# charlie_array_1206_v1.net
KiCad netlist of a schematic drawn in EAGLE
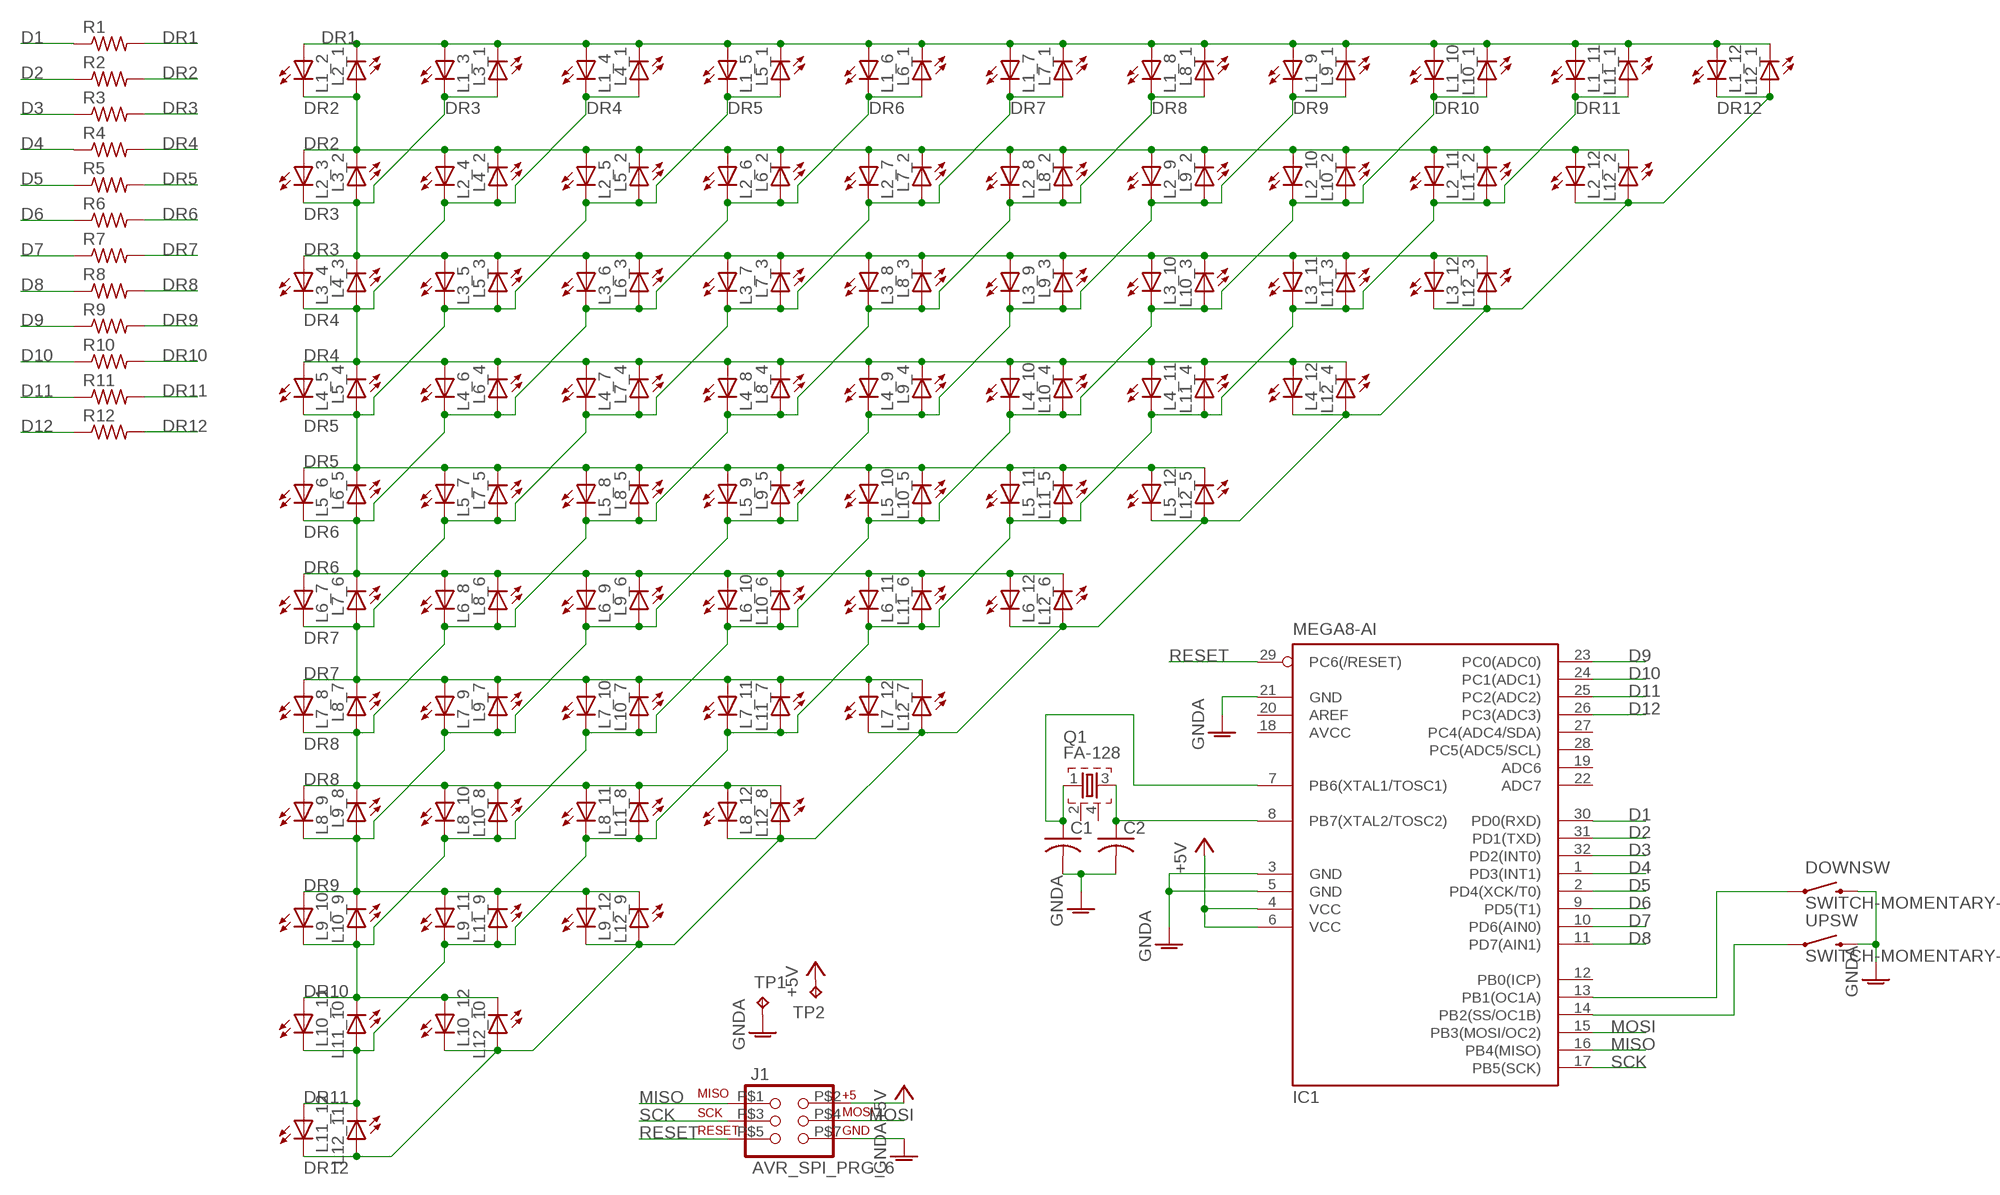
[diagram p0: schematic, sheet 1]

(export (version "E")
  (design (tool "Eeschema 10.0.6"))
  (components
    (comp (ref "C1")
      (value "C-USC0603")
      (footprint "eagle-import:C0603")
      (libsource (lib "eagle-import") (part "C-USC0603"))
    )
    (comp (ref "C2")
      (value "C-USC0603")
      (footprint "eagle-import:C0603")
      (libsource (lib "eagle-import") (part "C-USC0603"))
    )
    (comp (ref "DOWNSW")
      (value "SWITCH-MOMENTARY-2")
      (footprint "eagle-import:TACTILE_SWITCH_TALL")
      (libsource (lib "eagle-import") (part "SWITCH-MOMENTARY-2"))
    )
    (comp (ref "IC1")
      (value "MEGA8-AI")
      (footprint "eagle-import:TQFP32-08")
      (fields (field (name "MPN") "ATMEGA8-16AU"))
      (libsource (lib "eagle-import") (part "MEGA8-AI"))
    )
    (comp (ref "J1")
      (value "AVR_SPI_PRG_6")
      (footprint "eagle-import:2X3_ICSP_SMD")
      (libsource (lib "eagle-import") (part "AVR_SPI_PRG_6"))
    )
    (comp (ref "L1_2")
      (value "LEDCHIPLED_1206")
      (footprint "eagle-import:CHIPLED_1206")
      (libsource (lib "eagle-import") (part "LEDCHIPLED_1206"))
    )
    (comp (ref "L1_3")
      (value "LEDCHIPLED_1206")
      (footprint "eagle-import:CHIPLED_1206")
      (libsource (lib "eagle-import") (part "LEDCHIPLED_1206"))
    )
    (comp (ref "L1_4")
      (value "LEDCHIPLED_1206")
      (footprint "eagle-import:CHIPLED_1206")
      (libsource (lib "eagle-import") (part "LEDCHIPLED_1206"))
    )
    (comp (ref "L1_5")
      (value "LEDCHIPLED_1206")
      (footprint "eagle-import:CHIPLED_1206")
      (libsource (lib "eagle-import") (part "LEDCHIPLED_1206"))
    )
    (comp (ref "L1_6")
      (value "LEDCHIPLED_1206")
      (footprint "eagle-import:CHIPLED_1206")
      (libsource (lib "eagle-import") (part "LEDCHIPLED_1206"))
    )
    (comp (ref "L1_7")
      (value "LEDCHIPLED_1206")
      (footprint "eagle-import:CHIPLED_1206")
      (libsource (lib "eagle-import") (part "LEDCHIPLED_1206"))
    )
    (comp (ref "L1_8")
      (value "LEDCHIPLED_1206")
      (footprint "eagle-import:CHIPLED_1206")
      (libsource (lib "eagle-import") (part "LEDCHIPLED_1206"))
    )
    (comp (ref "L1_9")
      (value "LEDCHIPLED_1206")
      (footprint "eagle-import:CHIPLED_1206")
      (libsource (lib "eagle-import") (part "LEDCHIPLED_1206"))
    )
    (comp (ref "L1_10")
      (value "LEDCHIPLED_1206")
      (footprint "eagle-import:CHIPLED_1206")
      (libsource (lib "eagle-import") (part "LEDCHIPLED_1206"))
    )
    (comp (ref "L1_11")
      (value "LEDCHIPLED_1206")
      (footprint "eagle-import:CHIPLED_1206")
      (libsource (lib "eagle-import") (part "LEDCHIPLED_1206"))
    )
    (comp (ref "L1_12")
      (value "LEDCHIPLED_1206")
      (footprint "eagle-import:CHIPLED_1206")
      (libsource (lib "eagle-import") (part "LEDCHIPLED_1206"))
    )
    (comp (ref "L2_1")
      (value "LEDCHIPLED_1206")
      (footprint "eagle-import:CHIPLED_1206")
      (libsource (lib "eagle-import") (part "LEDCHIPLED_1206"))
    )
    (comp (ref "L2_3")
      (value "LEDCHIPLED_1206")
      (footprint "eagle-import:CHIPLED_1206")
      (libsource (lib "eagle-import") (part "LEDCHIPLED_1206"))
    )
    (comp (ref "L2_4")
      (value "LEDCHIPLED_1206")
      (footprint "eagle-import:CHIPLED_1206")
      (libsource (lib "eagle-import") (part "LEDCHIPLED_1206"))
    )
    (comp (ref "L2_5")
      (value "LEDCHIPLED_1206")
      (footprint "eagle-import:CHIPLED_1206")
      (libsource (lib "eagle-import") (part "LEDCHIPLED_1206"))
    )
    (comp (ref "L2_6")
      (value "LEDCHIPLED_1206")
      (footprint "eagle-import:CHIPLED_1206")
      (libsource (lib "eagle-import") (part "LEDCHIPLED_1206"))
    )
    (comp (ref "L2_7")
      (value "LEDCHIPLED_1206")
      (footprint "eagle-import:CHIPLED_1206")
      (libsource (lib "eagle-import") (part "LEDCHIPLED_1206"))
    )
    (comp (ref "L2_8")
      (value "LEDCHIPLED_1206")
      (footprint "eagle-import:CHIPLED_1206")
      (libsource (lib "eagle-import") (part "LEDCHIPLED_1206"))
    )
    (comp (ref "L2_9")
      (value "LEDCHIPLED_1206")
      (footprint "eagle-import:CHIPLED_1206")
      (libsource (lib "eagle-import") (part "LEDCHIPLED_1206"))
    )
    (comp (ref "L2_10")
      (value "LEDCHIPLED_1206")
      (footprint "eagle-import:CHIPLED_1206")
      (libsource (lib "eagle-import") (part "LEDCHIPLED_1206"))
    )
    (comp (ref "L2_11")
      (value "LEDCHIPLED_1206")
      (footprint "eagle-import:CHIPLED_1206")
      (libsource (lib "eagle-import") (part "LEDCHIPLED_1206"))
    )
    (comp (ref "L2_12")
      (value "LEDCHIPLED_1206")
      (footprint "eagle-import:CHIPLED_1206")
      (libsource (lib "eagle-import") (part "LEDCHIPLED_1206"))
    )
    (comp (ref "L3_1")
      (value "LEDCHIPLED_1206")
      (footprint "eagle-import:CHIPLED_1206")
      (libsource (lib "eagle-import") (part "LEDCHIPLED_1206"))
    )
    (comp (ref "L3_2")
      (value "LEDCHIPLED_1206")
      (footprint "eagle-import:CHIPLED_1206")
      (libsource (lib "eagle-import") (part "LEDCHIPLED_1206"))
    )
    (comp (ref "L3_4")
      (value "LEDCHIPLED_1206")
      (footprint "eagle-import:CHIPLED_1206")
      (libsource (lib "eagle-import") (part "LEDCHIPLED_1206"))
    )
    (comp (ref "L3_5")
      (value "LEDCHIPLED_1206")
      (footprint "eagle-import:CHIPLED_1206")
      (libsource (lib "eagle-import") (part "LEDCHIPLED_1206"))
    )
    (comp (ref "L3_6")
      (value "LEDCHIPLED_1206")
      (footprint "eagle-import:CHIPLED_1206")
      (libsource (lib "eagle-import") (part "LEDCHIPLED_1206"))
    )
    (comp (ref "L3_7")
      (value "LEDCHIPLED_1206")
      (footprint "eagle-import:CHIPLED_1206")
      (libsource (lib "eagle-import") (part "LEDCHIPLED_1206"))
    )
    (comp (ref "L3_8")
      (value "LEDCHIPLED_1206")
      (footprint "eagle-import:CHIPLED_1206")
      (libsource (lib "eagle-import") (part "LEDCHIPLED_1206"))
    )
    (comp (ref "L3_9")
      (value "LEDCHIPLED_1206")
      (footprint "eagle-import:CHIPLED_1206")
      (libsource (lib "eagle-import") (part "LEDCHIPLED_1206"))
    )
    (comp (ref "L3_10")
      (value "LEDCHIPLED_1206")
      (footprint "eagle-import:CHIPLED_1206")
      (libsource (lib "eagle-import") (part "LEDCHIPLED_1206"))
    )
    (comp (ref "L3_11")
      (value "LEDCHIPLED_1206")
      (footprint "eagle-import:CHIPLED_1206")
      (libsource (lib "eagle-import") (part "LEDCHIPLED_1206"))
    )
    (comp (ref "L3_12")
      (value "LEDCHIPLED_1206")
      (footprint "eagle-import:CHIPLED_1206")
      (libsource (lib "eagle-import") (part "LEDCHIPLED_1206"))
    )
    (comp (ref "L4_1")
      (value "LEDCHIPLED_1206")
      (footprint "eagle-import:CHIPLED_1206")
      (libsource (lib "eagle-import") (part "LEDCHIPLED_1206"))
    )
    (comp (ref "L4_2")
      (value "LEDCHIPLED_1206")
      (footprint "eagle-import:CHIPLED_1206")
      (libsource (lib "eagle-import") (part "LEDCHIPLED_1206"))
    )
    (comp (ref "L4_3")
      (value "LEDCHIPLED_1206")
      (footprint "eagle-import:CHIPLED_1206")
      (libsource (lib "eagle-import") (part "LEDCHIPLED_1206"))
    )
    (comp (ref "L4_5")
      (value "LEDCHIPLED_1206")
      (footprint "eagle-import:CHIPLED_1206")
      (libsource (lib "eagle-import") (part "LEDCHIPLED_1206"))
    )
    (comp (ref "L4_6")
      (value "LEDCHIPLED_1206")
      (footprint "eagle-import:CHIPLED_1206")
      (libsource (lib "eagle-import") (part "LEDCHIPLED_1206"))
    )
    (comp (ref "L4_7")
      (value "LEDCHIPLED_1206")
      (footprint "eagle-import:CHIPLED_1206")
      (libsource (lib "eagle-import") (part "LEDCHIPLED_1206"))
    )
    (comp (ref "L4_8")
      (value "LEDCHIPLED_1206")
      (footprint "eagle-import:CHIPLED_1206")
      (libsource (lib "eagle-import") (part "LEDCHIPLED_1206"))
    )
    (comp (ref "L4_9")
      (value "LEDCHIPLED_1206")
      (footprint "eagle-import:CHIPLED_1206")
      (libsource (lib "eagle-import") (part "LEDCHIPLED_1206"))
    )
    (comp (ref "L4_10")
      (value "LEDCHIPLED_1206")
      (footprint "eagle-import:CHIPLED_1206")
      (libsource (lib "eagle-import") (part "LEDCHIPLED_1206"))
    )
    (comp (ref "L4_11")
      (value "LEDCHIPLED_1206")
      (footprint "eagle-import:CHIPLED_1206")
      (libsource (lib "eagle-import") (part "LEDCHIPLED_1206"))
    )
    (comp (ref "L4_12")
      (value "LEDCHIPLED_1206")
      (footprint "eagle-import:CHIPLED_1206")
      (libsource (lib "eagle-import") (part "LEDCHIPLED_1206"))
    )
    (comp (ref "L5_1")
      (value "LEDCHIPLED_1206")
      (footprint "eagle-import:CHIPLED_1206")
      (libsource (lib "eagle-import") (part "LEDCHIPLED_1206"))
    )
    (comp (ref "L5_2")
      (value "LEDCHIPLED_1206")
      (footprint "eagle-import:CHIPLED_1206")
      (libsource (lib "eagle-import") (part "LEDCHIPLED_1206"))
    )
    (comp (ref "L5_3")
      (value "LEDCHIPLED_1206")
      (footprint "eagle-import:CHIPLED_1206")
      (libsource (lib "eagle-import") (part "LEDCHIPLED_1206"))
    )
    (comp (ref "L5_4")
      (value "LEDCHIPLED_1206")
      (footprint "eagle-import:CHIPLED_1206")
      (libsource (lib "eagle-import") (part "LEDCHIPLED_1206"))
    )
    (comp (ref "L5_6")
      (value "LEDCHIPLED_1206")
      (footprint "eagle-import:CHIPLED_1206")
      (libsource (lib "eagle-import") (part "LEDCHIPLED_1206"))
    )
    (comp (ref "L5_7")
      (value "LEDCHIPLED_1206")
      (footprint "eagle-import:CHIPLED_1206")
      (libsource (lib "eagle-import") (part "LEDCHIPLED_1206"))
    )
    (comp (ref "L5_8")
      (value "LEDCHIPLED_1206")
      (footprint "eagle-import:CHIPLED_1206")
      (libsource (lib "eagle-import") (part "LEDCHIPLED_1206"))
    )
    (comp (ref "L5_9")
      (value "LEDCHIPLED_1206")
      (footprint "eagle-import:CHIPLED_1206")
      (libsource (lib "eagle-import") (part "LEDCHIPLED_1206"))
    )
    (comp (ref "L5_10")
      (value "LEDCHIPLED_1206")
      (footprint "eagle-import:CHIPLED_1206")
      (libsource (lib "eagle-import") (part "LEDCHIPLED_1206"))
    )
    (comp (ref "L5_11")
      (value "LEDCHIPLED_1206")
      (footprint "eagle-import:CHIPLED_1206")
      (libsource (lib "eagle-import") (part "LEDCHIPLED_1206"))
    )
    (comp (ref "L5_12")
      (value "LEDCHIPLED_1206")
      (footprint "eagle-import:CHIPLED_1206")
      (libsource (lib "eagle-import") (part "LEDCHIPLED_1206"))
    )
    (comp (ref "L6_1")
      (value "LEDCHIPLED_1206")
      (footprint "eagle-import:CHIPLED_1206")
      (libsource (lib "eagle-import") (part "LEDCHIPLED_1206"))
    )
    (comp (ref "L6_2")
      (value "LEDCHIPLED_1206")
      (footprint "eagle-import:CHIPLED_1206")
      (libsource (lib "eagle-import") (part "LEDCHIPLED_1206"))
    )
    (comp (ref "L6_3")
      (value "LEDCHIPLED_1206")
      (footprint "eagle-import:CHIPLED_1206")
      (libsource (lib "eagle-import") (part "LEDCHIPLED_1206"))
    )
    (comp (ref "L6_4")
      (value "LEDCHIPLED_1206")
      (footprint "eagle-import:CHIPLED_1206")
      (libsource (lib "eagle-import") (part "LEDCHIPLED_1206"))
    )
    (comp (ref "L6_5")
      (value "LEDCHIPLED_1206")
      (footprint "eagle-import:CHIPLED_1206")
      (libsource (lib "eagle-import") (part "LEDCHIPLED_1206"))
    )
    (comp (ref "L6_7")
      (value "LEDCHIPLED_1206")
      (footprint "eagle-import:CHIPLED_1206")
      (libsource (lib "eagle-import") (part "LEDCHIPLED_1206"))
    )
    (comp (ref "L6_8")
      (value "LEDCHIPLED_1206")
      (footprint "eagle-import:CHIPLED_1206")
      (libsource (lib "eagle-import") (part "LEDCHIPLED_1206"))
    )
    (comp (ref "L6_9")
      (value "LEDCHIPLED_1206")
      (footprint "eagle-import:CHIPLED_1206")
      (libsource (lib "eagle-import") (part "LEDCHIPLED_1206"))
    )
    (comp (ref "L6_10")
      (value "LEDCHIPLED_1206")
      (footprint "eagle-import:CHIPLED_1206")
      (libsource (lib "eagle-import") (part "LEDCHIPLED_1206"))
    )
    (comp (ref "L6_11")
      (value "LEDCHIPLED_1206")
      (footprint "eagle-import:CHIPLED_1206")
      (libsource (lib "eagle-import") (part "LEDCHIPLED_1206"))
    )
    (comp (ref "L6_12")
      (value "LEDCHIPLED_1206")
      (footprint "eagle-import:CHIPLED_1206")
      (libsource (lib "eagle-import") (part "LEDCHIPLED_1206"))
    )
    (comp (ref "L7_1")
      (value "LEDCHIPLED_1206")
      (footprint "eagle-import:CHIPLED_1206")
      (libsource (lib "eagle-import") (part "LEDCHIPLED_1206"))
    )
    (comp (ref "L7_2")
      (value "LEDCHIPLED_1206")
      (footprint "eagle-import:CHIPLED_1206")
      (libsource (lib "eagle-import") (part "LEDCHIPLED_1206"))
    )
    (comp (ref "L7_3")
      (value "LEDCHIPLED_1206")
      (footprint "eagle-import:CHIPLED_1206")
      (libsource (lib "eagle-import") (part "LEDCHIPLED_1206"))
    )
    (comp (ref "L7_4")
      (value "LEDCHIPLED_1206")
      (footprint "eagle-import:CHIPLED_1206")
      (libsource (lib "eagle-import") (part "LEDCHIPLED_1206"))
    )
    (comp (ref "L7_5")
      (value "LEDCHIPLED_1206")
      (footprint "eagle-import:CHIPLED_1206")
      (libsource (lib "eagle-import") (part "LEDCHIPLED_1206"))
    )
    (comp (ref "L7_6")
      (value "LEDCHIPLED_1206")
      (footprint "eagle-import:CHIPLED_1206")
      (libsource (lib "eagle-import") (part "LEDCHIPLED_1206"))
    )
    (comp (ref "L7_8")
      (value "LEDCHIPLED_1206")
      (footprint "eagle-import:CHIPLED_1206")
      (libsource (lib "eagle-import") (part "LEDCHIPLED_1206"))
    )
    (comp (ref "L7_9")
      (value "LEDCHIPLED_1206")
      (footprint "eagle-import:CHIPLED_1206")
      (libsource (lib "eagle-import") (part "LEDCHIPLED_1206"))
    )
    (comp (ref "L7_10")
      (value "LEDCHIPLED_1206")
      (footprint "eagle-import:CHIPLED_1206")
      (libsource (lib "eagle-import") (part "LEDCHIPLED_1206"))
    )
    (comp (ref "L7_11")
      (value "LEDCHIPLED_1206")
      (footprint "eagle-import:CHIPLED_1206")
      (libsource (lib "eagle-import") (part "LEDCHIPLED_1206"))
    )
    (comp (ref "L7_12")
      (value "LEDCHIPLED_1206")
      (footprint "eagle-import:CHIPLED_1206")
      (libsource (lib "eagle-import") (part "LEDCHIPLED_1206"))
    )
    (comp (ref "L8_1")
      (value "LEDCHIPLED_1206")
      (footprint "eagle-import:CHIPLED_1206")
      (libsource (lib "eagle-import") (part "LEDCHIPLED_1206"))
    )
    (comp (ref "L8_2")
      (value "LEDCHIPLED_1206")
      (footprint "eagle-import:CHIPLED_1206")
      (libsource (lib "eagle-import") (part "LEDCHIPLED_1206"))
    )
    (comp (ref "L8_3")
      (value "LEDCHIPLED_1206")
      (footprint "eagle-import:CHIPLED_1206")
      (libsource (lib "eagle-import") (part "LEDCHIPLED_1206"))
    )
    (comp (ref "L8_4")
      (value "LEDCHIPLED_1206")
      (footprint "eagle-import:CHIPLED_1206")
      (libsource (lib "eagle-import") (part "LEDCHIPLED_1206"))
    )
    (comp (ref "L8_5")
      (value "LEDCHIPLED_1206")
      (footprint "eagle-import:CHIPLED_1206")
      (libsource (lib "eagle-import") (part "LEDCHIPLED_1206"))
    )
    (comp (ref "L8_6")
      (value "LEDCHIPLED_1206")
      (footprint "eagle-import:CHIPLED_1206")
      (libsource (lib "eagle-import") (part "LEDCHIPLED_1206"))
    )
    (comp (ref "L8_7")
      (value "LEDCHIPLED_1206")
      (footprint "eagle-import:CHIPLED_1206")
      (libsource (lib "eagle-import") (part "LEDCHIPLED_1206"))
    )
    (comp (ref "L8_9")
      (value "LEDCHIPLED_1206")
      (footprint "eagle-import:CHIPLED_1206")
      (libsource (lib "eagle-import") (part "LEDCHIPLED_1206"))
    )
    (comp (ref "L8_10")
      (value "LEDCHIPLED_1206")
      (footprint "eagle-import:CHIPLED_1206")
      (libsource (lib "eagle-import") (part "LEDCHIPLED_1206"))
    )
    (comp (ref "L8_11")
      (value "LEDCHIPLED_1206")
      (footprint "eagle-import:CHIPLED_1206")
      (libsource (lib "eagle-import") (part "LEDCHIPLED_1206"))
    )
    (comp (ref "L8_12")
      (value "LEDCHIPLED_1206")
      (footprint "eagle-import:CHIPLED_1206")
      (libsource (lib "eagle-import") (part "LEDCHIPLED_1206"))
    )
    (comp (ref "L9_1")
      (value "LEDCHIPLED_1206")
      (footprint "eagle-import:CHIPLED_1206")
      (libsource (lib "eagle-import") (part "LEDCHIPLED_1206"))
    )
    (comp (ref "L9_2")
      (value "LEDCHIPLED_1206")
      (footprint "eagle-import:CHIPLED_1206")
      (libsource (lib "eagle-import") (part "LEDCHIPLED_1206"))
    )
    (comp (ref "L9_3")
      (value "LEDCHIPLED_1206")
      (footprint "eagle-import:CHIPLED_1206")
      (libsource (lib "eagle-import") (part "LEDCHIPLED_1206"))
    )
    (comp (ref "L9_4")
      (value "LEDCHIPLED_1206")
      (footprint "eagle-import:CHIPLED_1206")
      (libsource (lib "eagle-import") (part "LEDCHIPLED_1206"))
    )
    (comp (ref "L9_5")
      (value "LEDCHIPLED_1206")
      (footprint "eagle-import:CHIPLED_1206")
      (libsource (lib "eagle-import") (part "LEDCHIPLED_1206"))
    )
    (comp (ref "L9_6")
      (value "LEDCHIPLED_1206")
      (footprint "eagle-import:CHIPLED_1206")
      (libsource (lib "eagle-import") (part "LEDCHIPLED_1206"))
    )
    (comp (ref "L9_7")
      (value "LEDCHIPLED_1206")
      (footprint "eagle-import:CHIPLED_1206")
      (libsource (lib "eagle-import") (part "LEDCHIPLED_1206"))
    )
    (comp (ref "L9_8")
      (value "LEDCHIPLED_1206")
      (footprint "eagle-import:CHIPLED_1206")
      (libsource (lib "eagle-import") (part "LEDCHIPLED_1206"))
    )
    (comp (ref "L9_10")
      (value "LEDCHIPLED_1206")
      (footprint "eagle-import:CHIPLED_1206")
      (libsource (lib "eagle-import") (part "LEDCHIPLED_1206"))
    )
    (comp (ref "L9_11")
      (value "LEDCHIPLED_1206")
      (footprint "eagle-import:CHIPLED_1206")
      (libsource (lib "eagle-import") (part "LEDCHIPLED_1206"))
    )
    (comp (ref "L9_12")
      (value "LEDCHIPLED_1206")
      (footprint "eagle-import:CHIPLED_1206")
      (libsource (lib "eagle-import") (part "LEDCHIPLED_1206"))
    )
    (comp (ref "L10_1")
      (value "LEDCHIPLED_1206")
      (footprint "eagle-import:CHIPLED_1206")
      (libsource (lib "eagle-import") (part "LEDCHIPLED_1206"))
    )
    (comp (ref "L10_2")
      (value "LEDCHIPLED_1206")
      (footprint "eagle-import:CHIPLED_1206")
      (libsource (lib "eagle-import") (part "LEDCHIPLED_1206"))
    )
    (comp (ref "L10_3")
      (value "LEDCHIPLED_1206")
      (footprint "eagle-import:CHIPLED_1206")
      (libsource (lib "eagle-import") (part "LEDCHIPLED_1206"))
    )
    (comp (ref "L10_4")
      (value "LEDCHIPLED_1206")
      (footprint "eagle-import:CHIPLED_1206")
      (libsource (lib "eagle-import") (part "LEDCHIPLED_1206"))
    )
    (comp (ref "L10_5")
      (value "LEDCHIPLED_1206")
      (footprint "eagle-import:CHIPLED_1206")
      (libsource (lib "eagle-import") (part "LEDCHIPLED_1206"))
    )
    (comp (ref "L10_6")
      (value "LEDCHIPLED_1206")
      (footprint "eagle-import:CHIPLED_1206")
      (libsource (lib "eagle-import") (part "LEDCHIPLED_1206"))
    )
    (comp (ref "L10_7")
      (value "LEDCHIPLED_1206")
      (footprint "eagle-import:CHIPLED_1206")
      (libsource (lib "eagle-import") (part "LEDCHIPLED_1206"))
    )
    (comp (ref "L10_8")
      (value "LEDCHIPLED_1206")
      (footprint "eagle-import:CHIPLED_1206")
      (libsource (lib "eagle-import") (part "LEDCHIPLED_1206"))
    )
    (comp (ref "L10_9")
      (value "LEDCHIPLED_1206")
      (footprint "eagle-import:CHIPLED_1206")
      (libsource (lib "eagle-import") (part "LEDCHIPLED_1206"))
    )
    (comp (ref "L10_11")
      (value "LEDCHIPLED_1206")
      (footprint "eagle-import:CHIPLED_1206")
      (libsource (lib "eagle-import") (part "LEDCHIPLED_1206"))
    )
    (comp (ref "L10_12")
      (value "LEDCHIPLED_1206")
      (footprint "eagle-import:CHIPLED_1206")
      (libsource (lib "eagle-import") (part "LEDCHIPLED_1206"))
    )
    (comp (ref "L11_1")
      (value "LEDCHIPLED_1206")
      (footprint "eagle-import:CHIPLED_1206")
      (libsource (lib "eagle-import") (part "LEDCHIPLED_1206"))
    )
    (comp (ref "L11_2")
      (value "LEDCHIPLED_1206")
      (footprint "eagle-import:CHIPLED_1206")
      (libsource (lib "eagle-import") (part "LEDCHIPLED_1206"))
    )
    (comp (ref "L11_3")
      (value "LEDCHIPLED_1206")
      (footprint "eagle-import:CHIPLED_1206")
      (libsource (lib "eagle-import") (part "LEDCHIPLED_1206"))
    )
    (comp (ref "L11_4")
      (value "LEDCHIPLED_1206")
      (footprint "eagle-import:CHIPLED_1206")
      (libsource (lib "eagle-import") (part "LEDCHIPLED_1206"))
    )
    (comp (ref "L11_5")
      (value "LEDCHIPLED_1206")
      (footprint "eagle-import:CHIPLED_1206")
      (libsource (lib "eagle-import") (part "LEDCHIPLED_1206"))
    )
    (comp (ref "L11_6")
      (value "LEDCHIPLED_1206")
      (footprint "eagle-import:CHIPLED_1206")
      (libsource (lib "eagle-import") (part "LEDCHIPLED_1206"))
    )
    (comp (ref "L11_7")
      (value "LEDCHIPLED_1206")
      (footprint "eagle-import:CHIPLED_1206")
      (libsource (lib "eagle-import") (part "LEDCHIPLED_1206"))
    )
    (comp (ref "L11_8")
      (value "LEDCHIPLED_1206")
      (footprint "eagle-import:CHIPLED_1206")
      (libsource (lib "eagle-import") (part "LEDCHIPLED_1206"))
    )
    (comp (ref "L11_9")
      (value "LEDCHIPLED_1206")
      (footprint "eagle-import:CHIPLED_1206")
      (libsource (lib "eagle-import") (part "LEDCHIPLED_1206"))
    )
    (comp (ref "L11_10")
      (value "LEDCHIPLED_1206")
      (footprint "eagle-import:CHIPLED_1206")
      (libsource (lib "eagle-import") (part "LEDCHIPLED_1206"))
    )
    (comp (ref "L11_12")
      (value "LEDCHIPLED_1206")
      (footprint "eagle-import:CHIPLED_1206")
      (libsource (lib "eagle-import") (part "LEDCHIPLED_1206"))
    )
    (comp (ref "L12_1")
      (value "LEDCHIPLED_1206")
      (footprint "eagle-import:CHIPLED_1206")
      (libsource (lib "eagle-import") (part "LEDCHIPLED_1206"))
    )
    (comp (ref "L12_2")
      (value "LEDCHIPLED_1206")
      (footprint "eagle-import:CHIPLED_1206")
      (libsource (lib "eagle-import") (part "LEDCHIPLED_1206"))
    )
    (comp (ref "L12_3")
      (value "LEDCHIPLED_1206")
      (footprint "eagle-import:CHIPLED_1206")
      (libsource (lib "eagle-import") (part "LEDCHIPLED_1206"))
    )
    (comp (ref "L12_4")
      (value "LEDCHIPLED_1206")
      (footprint "eagle-import:CHIPLED_1206")
      (libsource (lib "eagle-import") (part "LEDCHIPLED_1206"))
    )
    (comp (ref "L12_5")
      (value "LEDCHIPLED_1206")
      (footprint "eagle-import:CHIPLED_1206")
      (libsource (lib "eagle-import") (part "LEDCHIPLED_1206"))
    )
    (comp (ref "L12_6")
      (value "LEDCHIPLED_1206")
      (footprint "eagle-import:CHIPLED_1206")
      (libsource (lib "eagle-import") (part "LEDCHIPLED_1206"))
    )
    (comp (ref "L12_7")
      (value "LEDCHIPLED_1206")
      (footprint "eagle-import:CHIPLED_1206")
      (libsource (lib "eagle-import") (part "LEDCHIPLED_1206"))
    )
    (comp (ref "L12_8")
      (value "LEDCHIPLED_1206")
      (footprint "eagle-import:CHIPLED_1206")
      (libsource (lib "eagle-import") (part "LEDCHIPLED_1206"))
    )
    (comp (ref "L12_9")
      (value "LEDCHIPLED_1206")
      (footprint "eagle-import:CHIPLED_1206")
      (libsource (lib "eagle-import") (part "LEDCHIPLED_1206"))
    )
    (comp (ref "L12_10")
      (value "LEDCHIPLED_1206")
      (footprint "eagle-import:CHIPLED_1206")
      (libsource (lib "eagle-import") (part "LEDCHIPLED_1206"))
    )
    (comp (ref "L12_11")
      (value "LEDCHIPLED_1206")
      (footprint "eagle-import:CHIPLED_1206")
      (libsource (lib "eagle-import") (part "LEDCHIPLED_1206"))
    )
    (comp (ref "Q1")
      (value "FA-128")
      (footprint "eagle-import:FA-128")
      (libsource (lib "eagle-import") (part "FA-128"))
    )
    (comp (ref "R1")
      (value "R-US_R0603")
      (footprint "eagle-import:R0603")
      (libsource (lib "eagle-import") (part "R-US_R0603"))
    )
    (comp (ref "R2")
      (value "R-US_R0603")
      (footprint "eagle-import:R0603")
      (libsource (lib "eagle-import") (part "R-US_R0603"))
    )
    (comp (ref "R3")
      (value "R-US_R0603")
      (footprint "eagle-import:R0603")
      (libsource (lib "eagle-import") (part "R-US_R0603"))
    )
    (comp (ref "R4")
      (value "R-US_R0603")
      (footprint "eagle-import:R0603")
      (libsource (lib "eagle-import") (part "R-US_R0603"))
    )
    (comp (ref "R5")
      (value "R-US_R0603")
      (footprint "eagle-import:R0603")
      (libsource (lib "eagle-import") (part "R-US_R0603"))
    )
    (comp (ref "R6")
      (value "R-US_R0603")
      (footprint "eagle-import:R0603")
      (libsource (lib "eagle-import") (part "R-US_R0603"))
    )
    (comp (ref "R7")
      (value "R-US_R0603")
      (footprint "eagle-import:R0603")
      (libsource (lib "eagle-import") (part "R-US_R0603"))
    )
    (comp (ref "R8")
      (value "R-US_R0603")
      (footprint "eagle-import:R0603")
      (libsource (lib "eagle-import") (part "R-US_R0603"))
    )
    (comp (ref "R9")
      (value "R-US_R0603")
      (footprint "eagle-import:R0603")
      (libsource (lib "eagle-import") (part "R-US_R0603"))
    )
    (comp (ref "R10")
      (value "R-US_R0603")
      (footprint "eagle-import:R0603")
      (libsource (lib "eagle-import") (part "R-US_R0603"))
    )
    (comp (ref "R11")
      (value "R-US_R0603")
      (footprint "eagle-import:R0603")
      (libsource (lib "eagle-import") (part "R-US_R0603"))
    )
    (comp (ref "R12")
      (value "R-US_R0603")
      (footprint "eagle-import:R0603")
      (libsource (lib "eagle-import") (part "R-US_R0603"))
    )
    (comp (ref "TP1")
      (value "TPTP20SQ")
      (footprint "eagle-import:TP20SQ")
      (libsource (lib "eagle-import") (part "TPTP20SQ"))
    )
    (comp (ref "TP2")
      (value "TPTP20SQ")
      (footprint "eagle-import:TP20SQ")
      (libsource (lib "eagle-import") (part "TPTP20SQ"))
    )
    (comp (ref "UPSW")
      (value "SWITCH-MOMENTARY-2")
      (footprint "eagle-import:TACTILE_SWITCH_TALL")
      (libsource (lib "eagle-import") (part "SWITCH-MOMENTARY-2"))
    )
  )
  (nets
    (net (code "1") (name "+5V") (class "Default")
      (node (ref "IC1") (pin "4") (pinfunction "VCC_4") (pintype "power_in"))
      (node (ref "IC1") (pin "6") (pinfunction "VCC_6") (pintype "power_in"))
      (node (ref "J1") (pin "P$2") (pinfunction "2_P$2") (pintype "passive"))
      (node (ref "TP2") (pin "TP") (pinfunction "TP_TP") (pintype "input"))
    )
    (net (code "2") (name "/AVCC") (class "Default")
      (node (ref "IC1") (pin "18") (pinfunction "AVCC_18") (pintype "power_in"))
    )
    (net (code "3") (name "/D1") (class "Default")
      (node (ref "IC1") (pin "30") (pinfunction "PD0(RXD)_30") (pintype "bidirectional"))
      (node (ref "R1") (pin "1") (pinfunction "1_1") (pintype "passive"))
    )
    (net (code "4") (name "/D2") (class "Default")
      (node (ref "IC1") (pin "31") (pinfunction "PD1(TXD)_31") (pintype "bidirectional"))
      (node (ref "R2") (pin "1") (pinfunction "1_1") (pintype "passive"))
    )
    (net (code "5") (name "/D3") (class "Default")
      (node (ref "IC1") (pin "32") (pinfunction "PD2(INT0)_32") (pintype "bidirectional"))
      (node (ref "R3") (pin "1") (pinfunction "1_1") (pintype "passive"))
    )
    (net (code "6") (name "/D4") (class "Default")
      (node (ref "IC1") (pin "1") (pinfunction "PD3(INT1)_1") (pintype "bidirectional"))
      (node (ref "R4") (pin "1") (pinfunction "1_1") (pintype "passive"))
    )
    (net (code "7") (name "/D5") (class "Default")
      (node (ref "IC1") (pin "2") (pinfunction "PD4(XCK/T0)_2") (pintype "bidirectional"))
      (node (ref "R5") (pin "1") (pinfunction "1_1") (pintype "passive"))
    )
    (net (code "8") (name "/D6") (class "Default")
      (node (ref "IC1") (pin "9") (pinfunction "PD5(T1)_9") (pintype "bidirectional"))
      (node (ref "R6") (pin "1") (pinfunction "1_1") (pintype "passive"))
    )
    (net (code "9") (name "/D7") (class "Default")
      (node (ref "IC1") (pin "10") (pinfunction "PD6(AIN0)_10") (pintype "bidirectional"))
      (node (ref "R7") (pin "1") (pinfunction "1_1") (pintype "passive"))
    )
    (net (code "10") (name "/D8") (class "Default")
      (node (ref "IC1") (pin "11") (pinfunction "PD7(AIN1)_11") (pintype "bidirectional"))
      (node (ref "R8") (pin "1") (pinfunction "1_1") (pintype "passive"))
    )
    (net (code "11") (name "/D9") (class "Default")
      (node (ref "IC1") (pin "23") (pinfunction "PC0(ADC0)_23") (pintype "bidirectional"))
      (node (ref "R9") (pin "1") (pinfunction "1_1") (pintype "passive"))
    )
    (net (code "12") (name "/D10") (class "Default")
      (node (ref "IC1") (pin "24") (pinfunction "PC1(ADC1)_24") (pintype "bidirectional"))
      (node (ref "R10") (pin "1") (pinfunction "1_1") (pintype "passive"))
    )
    (net (code "13") (name "/D11") (class "Default")
      (node (ref "IC1") (pin "25") (pinfunction "PC2(ADC2)_25") (pintype "bidirectional"))
      (node (ref "R11") (pin "1") (pinfunction "1_1") (pintype "passive"))
    )
    (net (code "14") (name "/D12") (class "Default")
      (node (ref "IC1") (pin "26") (pinfunction "PC3(ADC3)_26") (pintype "bidirectional"))
      (node (ref "R12") (pin "1") (pinfunction "1_1") (pintype "passive"))
    )
    (net (code "15") (name "/DR1") (class "Default")
      (node (ref "L10_1") (pin "C") (pinfunction "C_C") (pintype "passive"))
      (node (ref "L11_1") (pin "C") (pinfunction "C_C") (pintype "passive"))
      (node (ref "L12_1") (pin "C") (pinfunction "C_C") (pintype "passive"))
      (node (ref "L1_10") (pin "A") (pinfunction "A_A") (pintype "passive"))
      (node (ref "L1_11") (pin "A") (pinfunction "A_A") (pintype "passive"))
      (node (ref "L1_12") (pin "A") (pinfunction "A_A") (pintype "passive"))
      (node (ref "L1_2") (pin "A") (pinfunction "A_A") (pintype "passive"))
      (node (ref "L1_3") (pin "A") (pinfunction "A_A") (pintype "passive"))
      (node (ref "L1_4") (pin "A") (pinfunction "A_A") (pintype "passive"))
      (node (ref "L1_5") (pin "A") (pinfunction "A_A") (pintype "passive"))
      (node (ref "L1_6") (pin "A") (pinfunction "A_A") (pintype "passive"))
      (node (ref "L1_7") (pin "A") (pinfunction "A_A") (pintype "passive"))
      (node (ref "L1_8") (pin "A") (pinfunction "A_A") (pintype "passive"))
      (node (ref "L1_9") (pin "A") (pinfunction "A_A") (pintype "passive"))
      (node (ref "L2_1") (pin "C") (pinfunction "C_C") (pintype "passive"))
      (node (ref "L3_1") (pin "C") (pinfunction "C_C") (pintype "passive"))
      (node (ref "L4_1") (pin "C") (pinfunction "C_C") (pintype "passive"))
      (node (ref "L5_1") (pin "C") (pinfunction "C_C") (pintype "passive"))
      (node (ref "L6_1") (pin "C") (pinfunction "C_C") (pintype "passive"))
      (node (ref "L7_1") (pin "C") (pinfunction "C_C") (pintype "passive"))
      (node (ref "L8_1") (pin "C") (pinfunction "C_C") (pintype "passive"))
      (node (ref "L9_1") (pin "C") (pinfunction "C_C") (pintype "passive"))
      (node (ref "R1") (pin "2") (pinfunction "2_2") (pintype "passive"))
    )
    (net (code "16") (name "/DR2") (class "Default")
      (node (ref "L10_2") (pin "C") (pinfunction "C_C") (pintype "passive"))
      (node (ref "L11_2") (pin "C") (pinfunction "C_C") (pintype "passive"))
      (node (ref "L12_2") (pin "C") (pinfunction "C_C") (pintype "passive"))
      (node (ref "L1_2") (pin "C") (pinfunction "C_C") (pintype "passive"))
      (node (ref "L2_1") (pin "A") (pinfunction "A_A") (pintype "passive"))
      (node (ref "L2_10") (pin "A") (pinfunction "A_A") (pintype "passive"))
      (node (ref "L2_11") (pin "A") (pinfunction "A_A") (pintype "passive"))
      (node (ref "L2_12") (pin "A") (pinfunction "A_A") (pintype "passive"))
      (node (ref "L2_3") (pin "A") (pinfunction "A_A") (pintype "passive"))
      (node (ref "L2_4") (pin "A") (pinfunction "A_A") (pintype "passive"))
      (node (ref "L2_5") (pin "A") (pinfunction "A_A") (pintype "passive"))
      (node (ref "L2_6") (pin "A") (pinfunction "A_A") (pintype "passive"))
      (node (ref "L2_7") (pin "A") (pinfunction "A_A") (pintype "passive"))
      (node (ref "L2_8") (pin "A") (pinfunction "A_A") (pintype "passive"))
      (node (ref "L2_9") (pin "A") (pinfunction "A_A") (pintype "passive"))
      (node (ref "L3_2") (pin "C") (pinfunction "C_C") (pintype "passive"))
      (node (ref "L4_2") (pin "C") (pinfunction "C_C") (pintype "passive"))
      (node (ref "L5_2") (pin "C") (pinfunction "C_C") (pintype "passive"))
      (node (ref "L6_2") (pin "C") (pinfunction "C_C") (pintype "passive"))
      (node (ref "L7_2") (pin "C") (pinfunction "C_C") (pintype "passive"))
      (node (ref "L8_2") (pin "C") (pinfunction "C_C") (pintype "passive"))
      (node (ref "L9_2") (pin "C") (pinfunction "C_C") (pintype "passive"))
      (node (ref "R2") (pin "2") (pinfunction "2_2") (pintype "passive"))
    )
    (net (code "17") (name "/DR3") (class "Default")
      (node (ref "L10_3") (pin "C") (pinfunction "C_C") (pintype "passive"))
      (node (ref "L11_3") (pin "C") (pinfunction "C_C") (pintype "passive"))
      (node (ref "L12_3") (pin "C") (pinfunction "C_C") (pintype "passive"))
      (node (ref "L1_3") (pin "C") (pinfunction "C_C") (pintype "passive"))
      (node (ref "L2_3") (pin "C") (pinfunction "C_C") (pintype "passive"))
      (node (ref "L3_1") (pin "A") (pinfunction "A_A") (pintype "passive"))
      (node (ref "L3_10") (pin "A") (pinfunction "A_A") (pintype "passive"))
      (node (ref "L3_11") (pin "A") (pinfunction "A_A") (pintype "passive"))
      (node (ref "L3_12") (pin "A") (pinfunction "A_A") (pintype "passive"))
      (node (ref "L3_2") (pin "A") (pinfunction "A_A") (pintype "passive"))
      (node (ref "L3_4") (pin "A") (pinfunction "A_A") (pintype "passive"))
      (node (ref "L3_5") (pin "A") (pinfunction "A_A") (pintype "passive"))
      (node (ref "L3_6") (pin "A") (pinfunction "A_A") (pintype "passive"))
      (node (ref "L3_7") (pin "A") (pinfunction "A_A") (pintype "passive"))
      (node (ref "L3_8") (pin "A") (pinfunction "A_A") (pintype "passive"))
      (node (ref "L3_9") (pin "A") (pinfunction "A_A") (pintype "passive"))
      (node (ref "L4_3") (pin "C") (pinfunction "C_C") (pintype "passive"))
      (node (ref "L5_3") (pin "C") (pinfunction "C_C") (pintype "passive"))
      (node (ref "L6_3") (pin "C") (pinfunction "C_C") (pintype "passive"))
      (node (ref "L7_3") (pin "C") (pinfunction "C_C") (pintype "passive"))
      (node (ref "L8_3") (pin "C") (pinfunction "C_C") (pintype "passive"))
      (node (ref "L9_3") (pin "C") (pinfunction "C_C") (pintype "passive"))
      (node (ref "R3") (pin "2") (pinfunction "2_2") (pintype "passive"))
    )
    (net (code "18") (name "/DR4") (class "Default")
      (node (ref "L10_4") (pin "C") (pinfunction "C_C") (pintype "passive"))
      (node (ref "L11_4") (pin "C") (pinfunction "C_C") (pintype "passive"))
      (node (ref "L12_4") (pin "C") (pinfunction "C_C") (pintype "passive"))
      (node (ref "L1_4") (pin "C") (pinfunction "C_C") (pintype "passive"))
      (node (ref "L2_4") (pin "C") (pinfunction "C_C") (pintype "passive"))
      (node (ref "L3_4") (pin "C") (pinfunction "C_C") (pintype "passive"))
      (node (ref "L4_1") (pin "A") (pinfunction "A_A") (pintype "passive"))
      (node (ref "L4_10") (pin "A") (pinfunction "A_A") (pintype "passive"))
      (node (ref "L4_11") (pin "A") (pinfunction "A_A") (pintype "passive"))
      (node (ref "L4_12") (pin "A") (pinfunction "A_A") (pintype "passive"))
      (node (ref "L4_2") (pin "A") (pinfunction "A_A") (pintype "passive"))
      (node (ref "L4_3") (pin "A") (pinfunction "A_A") (pintype "passive"))
      (node (ref "L4_5") (pin "A") (pinfunction "A_A") (pintype "passive"))
      (node (ref "L4_6") (pin "A") (pinfunction "A_A") (pintype "passive"))
      (node (ref "L4_7") (pin "A") (pinfunction "A_A") (pintype "passive"))
      (node (ref "L4_8") (pin "A") (pinfunction "A_A") (pintype "passive"))
      (node (ref "L4_9") (pin "A") (pinfunction "A_A") (pintype "passive"))
      (node (ref "L5_4") (pin "C") (pinfunction "C_C") (pintype "passive"))
      (node (ref "L6_4") (pin "C") (pinfunction "C_C") (pintype "passive"))
      (node (ref "L7_4") (pin "C") (pinfunction "C_C") (pintype "passive"))
      (node (ref "L8_4") (pin "C") (pinfunction "C_C") (pintype "passive"))
      (node (ref "L9_4") (pin "C") (pinfunction "C_C") (pintype "passive"))
      (node (ref "R4") (pin "2") (pinfunction "2_2") (pintype "passive"))
    )
    (net (code "19") (name "/DR5") (class "Default")
      (node (ref "L10_5") (pin "C") (pinfunction "C_C") (pintype "passive"))
      (node (ref "L11_5") (pin "C") (pinfunction "C_C") (pintype "passive"))
      (node (ref "L12_5") (pin "C") (pinfunction "C_C") (pintype "passive"))
      (node (ref "L1_5") (pin "C") (pinfunction "C_C") (pintype "passive"))
      (node (ref "L2_5") (pin "C") (pinfunction "C_C") (pintype "passive"))
      (node (ref "L3_5") (pin "C") (pinfunction "C_C") (pintype "passive"))
      (node (ref "L4_5") (pin "C") (pinfunction "C_C") (pintype "passive"))
      (node (ref "L5_1") (pin "A") (pinfunction "A_A") (pintype "passive"))
      (node (ref "L5_10") (pin "A") (pinfunction "A_A") (pintype "passive"))
      (node (ref "L5_11") (pin "A") (pinfunction "A_A") (pintype "passive"))
      (node (ref "L5_12") (pin "A") (pinfunction "A_A") (pintype "passive"))
      (node (ref "L5_2") (pin "A") (pinfunction "A_A") (pintype "passive"))
      (node (ref "L5_3") (pin "A") (pinfunction "A_A") (pintype "passive"))
      (node (ref "L5_4") (pin "A") (pinfunction "A_A") (pintype "passive"))
      (node (ref "L5_6") (pin "A") (pinfunction "A_A") (pintype "passive"))
      (node (ref "L5_7") (pin "A") (pinfunction "A_A") (pintype "passive"))
      (node (ref "L5_8") (pin "A") (pinfunction "A_A") (pintype "passive"))
      (node (ref "L5_9") (pin "A") (pinfunction "A_A") (pintype "passive"))
      (node (ref "L6_5") (pin "C") (pinfunction "C_C") (pintype "passive"))
      (node (ref "L7_5") (pin "C") (pinfunction "C_C") (pintype "passive"))
      (node (ref "L8_5") (pin "C") (pinfunction "C_C") (pintype "passive"))
      (node (ref "L9_5") (pin "C") (pinfunction "C_C") (pintype "passive"))
      (node (ref "R5") (pin "2") (pinfunction "2_2") (pintype "passive"))
    )
    (net (code "20") (name "/DR6") (class "Default")
      (node (ref "L10_6") (pin "C") (pinfunction "C_C") (pintype "passive"))
      (node (ref "L11_6") (pin "C") (pinfunction "C_C") (pintype "passive"))
      (node (ref "L12_6") (pin "C") (pinfunction "C_C") (pintype "passive"))
      (node (ref "L1_6") (pin "C") (pinfunction "C_C") (pintype "passive"))
      (node (ref "L2_6") (pin "C") (pinfunction "C_C") (pintype "passive"))
      (node (ref "L3_6") (pin "C") (pinfunction "C_C") (pintype "passive"))
      (node (ref "L4_6") (pin "C") (pinfunction "C_C") (pintype "passive"))
      (node (ref "L5_6") (pin "C") (pinfunction "C_C") (pintype "passive"))
      (node (ref "L6_1") (pin "A") (pinfunction "A_A") (pintype "passive"))
      (node (ref "L6_10") (pin "A") (pinfunction "A_A") (pintype "passive"))
      (node (ref "L6_11") (pin "A") (pinfunction "A_A") (pintype "passive"))
      (node (ref "L6_12") (pin "A") (pinfunction "A_A") (pintype "passive"))
      (node (ref "L6_2") (pin "A") (pinfunction "A_A") (pintype "passive"))
      (node (ref "L6_3") (pin "A") (pinfunction "A_A") (pintype "passive"))
      (node (ref "L6_4") (pin "A") (pinfunction "A_A") (pintype "passive"))
      (node (ref "L6_5") (pin "A") (pinfunction "A_A") (pintype "passive"))
      (node (ref "L6_7") (pin "A") (pinfunction "A_A") (pintype "passive"))
      (node (ref "L6_8") (pin "A") (pinfunction "A_A") (pintype "passive"))
      (node (ref "L6_9") (pin "A") (pinfunction "A_A") (pintype "passive"))
      (node (ref "L7_6") (pin "C") (pinfunction "C_C") (pintype "passive"))
      (node (ref "L8_6") (pin "C") (pinfunction "C_C") (pintype "passive"))
      (node (ref "L9_6") (pin "C") (pinfunction "C_C") (pintype "passive"))
      (node (ref "R6") (pin "2") (pinfunction "2_2") (pintype "passive"))
    )
    (net (code "21") (name "/DR7") (class "Default")
      (node (ref "L10_7") (pin "C") (pinfunction "C_C") (pintype "passive"))
      (node (ref "L11_7") (pin "C") (pinfunction "C_C") (pintype "passive"))
      (node (ref "L12_7") (pin "C") (pinfunction "C_C") (pintype "passive"))
      (node (ref "L1_7") (pin "C") (pinfunction "C_C") (pintype "passive"))
      (node (ref "L2_7") (pin "C") (pinfunction "C_C") (pintype "passive"))
      (node (ref "L3_7") (pin "C") (pinfunction "C_C") (pintype "passive"))
      (node (ref "L4_7") (pin "C") (pinfunction "C_C") (pintype "passive"))
      (node (ref "L5_7") (pin "C") (pinfunction "C_C") (pintype "passive"))
      (node (ref "L6_7") (pin "C") (pinfunction "C_C") (pintype "passive"))
      (node (ref "L7_1") (pin "A") (pinfunction "A_A") (pintype "passive"))
      (node (ref "L7_10") (pin "A") (pinfunction "A_A") (pintype "passive"))
      (node (ref "L7_11") (pin "A") (pinfunction "A_A") (pintype "passive"))
      (node (ref "L7_12") (pin "A") (pinfunction "A_A") (pintype "passive"))
      (node (ref "L7_2") (pin "A") (pinfunction "A_A") (pintype "passive"))
      (node (ref "L7_3") (pin "A") (pinfunction "A_A") (pintype "passive"))
      (node (ref "L7_4") (pin "A") (pinfunction "A_A") (pintype "passive"))
      (node (ref "L7_5") (pin "A") (pinfunction "A_A") (pintype "passive"))
      (node (ref "L7_6") (pin "A") (pinfunction "A_A") (pintype "passive"))
      (node (ref "L7_8") (pin "A") (pinfunction "A_A") (pintype "passive"))
      (node (ref "L7_9") (pin "A") (pinfunction "A_A") (pintype "passive"))
      (node (ref "L8_7") (pin "C") (pinfunction "C_C") (pintype "passive"))
      (node (ref "L9_7") (pin "C") (pinfunction "C_C") (pintype "passive"))
      (node (ref "R7") (pin "2") (pinfunction "2_2") (pintype "passive"))
    )
    (net (code "22") (name "/DR8") (class "Default")
      (node (ref "L10_8") (pin "C") (pinfunction "C_C") (pintype "passive"))
      (node (ref "L11_8") (pin "C") (pinfunction "C_C") (pintype "passive"))
      (node (ref "L12_8") (pin "C") (pinfunction "C_C") (pintype "passive"))
      (node (ref "L1_8") (pin "C") (pinfunction "C_C") (pintype "passive"))
      (node (ref "L2_8") (pin "C") (pinfunction "C_C") (pintype "passive"))
      (node (ref "L3_8") (pin "C") (pinfunction "C_C") (pintype "passive"))
      (node (ref "L4_8") (pin "C") (pinfunction "C_C") (pintype "passive"))
      (node (ref "L5_8") (pin "C") (pinfunction "C_C") (pintype "passive"))
      (node (ref "L6_8") (pin "C") (pinfunction "C_C") (pintype "passive"))
      (node (ref "L7_8") (pin "C") (pinfunction "C_C") (pintype "passive"))
      (node (ref "L8_1") (pin "A") (pinfunction "A_A") (pintype "passive"))
      (node (ref "L8_10") (pin "A") (pinfunction "A_A") (pintype "passive"))
      (node (ref "L8_11") (pin "A") (pinfunction "A_A") (pintype "passive"))
      (node (ref "L8_12") (pin "A") (pinfunction "A_A") (pintype "passive"))
      (node (ref "L8_2") (pin "A") (pinfunction "A_A") (pintype "passive"))
      (node (ref "L8_3") (pin "A") (pinfunction "A_A") (pintype "passive"))
      (node (ref "L8_4") (pin "A") (pinfunction "A_A") (pintype "passive"))
      (node (ref "L8_5") (pin "A") (pinfunction "A_A") (pintype "passive"))
      (node (ref "L8_6") (pin "A") (pinfunction "A_A") (pintype "passive"))
      (node (ref "L8_7") (pin "A") (pinfunction "A_A") (pintype "passive"))
      (node (ref "L8_9") (pin "A") (pinfunction "A_A") (pintype "passive"))
      (node (ref "L9_8") (pin "C") (pinfunction "C_C") (pintype "passive"))
      (node (ref "R8") (pin "2") (pinfunction "2_2") (pintype "passive"))
    )
    (net (code "23") (name "/DR9") (class "Default")
      (node (ref "L10_9") (pin "C") (pinfunction "C_C") (pintype "passive"))
      (node (ref "L11_9") (pin "C") (pinfunction "C_C") (pintype "passive"))
      (node (ref "L12_9") (pin "C") (pinfunction "C_C") (pintype "passive"))
      (node (ref "L1_9") (pin "C") (pinfunction "C_C") (pintype "passive"))
      (node (ref "L2_9") (pin "C") (pinfunction "C_C") (pintype "passive"))
      (node (ref "L3_9") (pin "C") (pinfunction "C_C") (pintype "passive"))
      (node (ref "L4_9") (pin "C") (pinfunction "C_C") (pintype "passive"))
      (node (ref "L5_9") (pin "C") (pinfunction "C_C") (pintype "passive"))
      (node (ref "L6_9") (pin "C") (pinfunction "C_C") (pintype "passive"))
      (node (ref "L7_9") (pin "C") (pinfunction "C_C") (pintype "passive"))
      (node (ref "L8_9") (pin "C") (pinfunction "C_C") (pintype "passive"))
      (node (ref "L9_1") (pin "A") (pinfunction "A_A") (pintype "passive"))
      (node (ref "L9_10") (pin "A") (pinfunction "A_A") (pintype "passive"))
      (node (ref "L9_11") (pin "A") (pinfunction "A_A") (pintype "passive"))
      (node (ref "L9_12") (pin "A") (pinfunction "A_A") (pintype "passive"))
      (node (ref "L9_2") (pin "A") (pinfunction "A_A") (pintype "passive"))
      (node (ref "L9_3") (pin "A") (pinfunction "A_A") (pintype "passive"))
      (node (ref "L9_4") (pin "A") (pinfunction "A_A") (pintype "passive"))
      (node (ref "L9_5") (pin "A") (pinfunction "A_A") (pintype "passive"))
      (node (ref "L9_6") (pin "A") (pinfunction "A_A") (pintype "passive"))
      (node (ref "L9_7") (pin "A") (pinfunction "A_A") (pintype "passive"))
      (node (ref "L9_8") (pin "A") (pinfunction "A_A") (pintype "passive"))
      (node (ref "R9") (pin "2") (pinfunction "2_2") (pintype "passive"))
    )
    (net (code "24") (name "/DR10") (class "Default")
      (node (ref "L10_1") (pin "A") (pinfunction "A_A") (pintype "passive"))
      (node (ref "L10_11") (pin "A") (pinfunction "A_A") (pintype "passive"))
      (node (ref "L10_12") (pin "A") (pinfunction "A_A") (pintype "passive"))
      (node (ref "L10_2") (pin "A") (pinfunction "A_A") (pintype "passive"))
      (node (ref "L10_3") (pin "A") (pinfunction "A_A") (pintype "passive"))
      (node (ref "L10_4") (pin "A") (pinfunction "A_A") (pintype "passive"))
      (node (ref "L10_5") (pin "A") (pinfunction "A_A") (pintype "passive"))
      (node (ref "L10_6") (pin "A") (pinfunction "A_A") (pintype "passive"))
      (node (ref "L10_7") (pin "A") (pinfunction "A_A") (pintype "passive"))
      (node (ref "L10_8") (pin "A") (pinfunction "A_A") (pintype "passive"))
      (node (ref "L10_9") (pin "A") (pinfunction "A_A") (pintype "passive"))
      (node (ref "L11_10") (pin "C") (pinfunction "C_C") (pintype "passive"))
      (node (ref "L12_10") (pin "C") (pinfunction "C_C") (pintype "passive"))
      (node (ref "L1_10") (pin "C") (pinfunction "C_C") (pintype "passive"))
      (node (ref "L2_10") (pin "C") (pinfunction "C_C") (pintype "passive"))
      (node (ref "L3_10") (pin "C") (pinfunction "C_C") (pintype "passive"))
      (node (ref "L4_10") (pin "C") (pinfunction "C_C") (pintype "passive"))
      (node (ref "L5_10") (pin "C") (pinfunction "C_C") (pintype "passive"))
      (node (ref "L6_10") (pin "C") (pinfunction "C_C") (pintype "passive"))
      (node (ref "L7_10") (pin "C") (pinfunction "C_C") (pintype "passive"))
      (node (ref "L8_10") (pin "C") (pinfunction "C_C") (pintype "passive"))
      (node (ref "L9_10") (pin "C") (pinfunction "C_C") (pintype "passive"))
      (node (ref "R10") (pin "2") (pinfunction "2_2") (pintype "passive"))
    )
    (net (code "25") (name "/DR11") (class "Default")
      (node (ref "L10_11") (pin "C") (pinfunction "C_C") (pintype "passive"))
      (node (ref "L11_1") (pin "A") (pinfunction "A_A") (pintype "passive"))
      (node (ref "L11_10") (pin "A") (pinfunction "A_A") (pintype "passive"))
      (node (ref "L11_12") (pin "A") (pinfunction "A_A") (pintype "passive"))
      (node (ref "L11_2") (pin "A") (pinfunction "A_A") (pintype "passive"))
      (node (ref "L11_3") (pin "A") (pinfunction "A_A") (pintype "passive"))
      (node (ref "L11_4") (pin "A") (pinfunction "A_A") (pintype "passive"))
      (node (ref "L11_5") (pin "A") (pinfunction "A_A") (pintype "passive"))
      (node (ref "L11_6") (pin "A") (pinfunction "A_A") (pintype "passive"))
      (node (ref "L11_7") (pin "A") (pinfunction "A_A") (pintype "passive"))
      (node (ref "L11_8") (pin "A") (pinfunction "A_A") (pintype "passive"))
      (node (ref "L11_9") (pin "A") (pinfunction "A_A") (pintype "passive"))
      (node (ref "L12_11") (pin "C") (pinfunction "C_C") (pintype "passive"))
      (node (ref "L1_11") (pin "C") (pinfunction "C_C") (pintype "passive"))
      (node (ref "L2_11") (pin "C") (pinfunction "C_C") (pintype "passive"))
      (node (ref "L3_11") (pin "C") (pinfunction "C_C") (pintype "passive"))
      (node (ref "L4_11") (pin "C") (pinfunction "C_C") (pintype "passive"))
      (node (ref "L5_11") (pin "C") (pinfunction "C_C") (pintype "passive"))
      (node (ref "L6_11") (pin "C") (pinfunction "C_C") (pintype "passive"))
      (node (ref "L7_11") (pin "C") (pinfunction "C_C") (pintype "passive"))
      (node (ref "L8_11") (pin "C") (pinfunction "C_C") (pintype "passive"))
      (node (ref "L9_11") (pin "C") (pinfunction "C_C") (pintype "passive"))
      (node (ref "R11") (pin "2") (pinfunction "2_2") (pintype "passive"))
    )
    (net (code "26") (name "/DR12") (class "Default")
      (node (ref "L10_12") (pin "C") (pinfunction "C_C") (pintype "passive"))
      (node (ref "L11_12") (pin "C") (pinfunction "C_C") (pintype "passive"))
      (node (ref "L12_1") (pin "A") (pinfunction "A_A") (pintype "passive"))
      (node (ref "L12_10") (pin "A") (pinfunction "A_A") (pintype "passive"))
      (node (ref "L12_11") (pin "A") (pinfunction "A_A") (pintype "passive"))
      (node (ref "L12_2") (pin "A") (pinfunction "A_A") (pintype "passive"))
      (node (ref "L12_3") (pin "A") (pinfunction "A_A") (pintype "passive"))
      (node (ref "L12_4") (pin "A") (pinfunction "A_A") (pintype "passive"))
      (node (ref "L12_5") (pin "A") (pinfunction "A_A") (pintype "passive"))
      (node (ref "L12_6") (pin "A") (pinfunction "A_A") (pintype "passive"))
      (node (ref "L12_7") (pin "A") (pinfunction "A_A") (pintype "passive"))
      (node (ref "L12_8") (pin "A") (pinfunction "A_A") (pintype "passive"))
      (node (ref "L12_9") (pin "A") (pinfunction "A_A") (pintype "passive"))
      (node (ref "L1_12") (pin "C") (pinfunction "C_C") (pintype "passive"))
      (node (ref "L2_12") (pin "C") (pinfunction "C_C") (pintype "passive"))
      (node (ref "L3_12") (pin "C") (pinfunction "C_C") (pintype "passive"))
      (node (ref "L4_12") (pin "C") (pinfunction "C_C") (pintype "passive"))
      (node (ref "L5_12") (pin "C") (pinfunction "C_C") (pintype "passive"))
      (node (ref "L6_12") (pin "C") (pinfunction "C_C") (pintype "passive"))
      (node (ref "L7_12") (pin "C") (pinfunction "C_C") (pintype "passive"))
      (node (ref "L8_12") (pin "C") (pinfunction "C_C") (pintype "passive"))
      (node (ref "L9_12") (pin "C") (pinfunction "C_C") (pintype "passive"))
      (node (ref "R12") (pin "2") (pinfunction "2_2") (pintype "passive"))
    )
    (net (code "27") (name "/MISO") (class "Default")
      (node (ref "IC1") (pin "16") (pinfunction "PB4(MISO)_16") (pintype "bidirectional"))
      (node (ref "J1") (pin "P$1") (pinfunction "1_P$1") (pintype "passive"))
    )
    (net (code "28") (name "/MOSI") (class "Default")
      (node (ref "IC1") (pin "15") (pinfunction "PB3(MOSI/OC2)_15") (pintype "bidirectional"))
      (node (ref "J1") (pin "P$4") (pinfunction "4_P$4") (pintype "passive"))
    )
    (net (code "29") (name "/RESET") (class "Default")
      (node (ref "IC1") (pin "29") (pinfunction "PC6(/RESET)_29") (pintype "bidirectional"))
      (node (ref "J1") (pin "P$5") (pinfunction "5_P$5") (pintype "passive"))
    )
    (net (code "30") (name "/SCK") (class "Default")
      (node (ref "IC1") (pin "17") (pinfunction "PB5(SCK)_17") (pintype "bidirectional"))
      (node (ref "J1") (pin "P$3") (pinfunction "3_P$3") (pintype "passive"))
    )
    (net (code "31") (name "GNDA") (class "Default")
      (node (ref "C1") (pin "2") (pinfunction "2_2") (pintype "passive"))
      (node (ref "C2") (pin "2") (pinfunction "2_2") (pintype "passive"))
      (node (ref "DOWNSW") (pin "B2") (pinfunction "2_B2") (pintype "passive"))
      (node (ref "IC1") (pin "21") (pinfunction "GND_21") (pintype "power_in"))
      (node (ref "IC1") (pin "3") (pinfunction "GND_3") (pintype "power_in"))
      (node (ref "IC1") (pin "5") (pinfunction "GND_5") (pintype "power_in"))
      (node (ref "J1") (pin "P$7") (pinfunction "6_P$7") (pintype "passive"))
      (node (ref "TP1") (pin "TP") (pinfunction "TP_TP") (pintype "input"))
      (node (ref "UPSW") (pin "B2") (pinfunction "2_B2") (pintype "passive"))
    )
    (net (code "32") (name "Net-(DOWNSW-1)") (class "Default")
      (node (ref "DOWNSW") (pin "A2") (pinfunction "1_A2") (pintype "passive"))
      (node (ref "IC1") (pin "13") (pinfunction "PB1(OC1A)_13") (pintype "bidirectional"))
    )
    (net (code "33") (name "Net-(IC1-PB2(SS{slash}OC1B))") (class "Default")
      (node (ref "IC1") (pin "14") (pinfunction "PB2(SS/OC1B)_14") (pintype "bidirectional"))
      (node (ref "UPSW") (pin "A2") (pinfunction "1_A2") (pintype "passive"))
    )
    (net (code "34") (name "Net-(IC1-PB6(XTAL1{slash}TOSC1))") (class "Default")
      (node (ref "C1") (pin "1") (pinfunction "1_1") (pintype "passive"))
      (node (ref "IC1") (pin "7") (pinfunction "PB6(XTAL1/TOSC1)_7") (pintype "bidirectional"))
      (node (ref "Q1") (pin "1") (pinfunction "1_1") (pintype "passive"))
    )
    (net (code "35") (name "Net-(IC1-PB7(XTAL2{slash}TOSC2))") (class "Default")
      (node (ref "C2") (pin "1") (pinfunction "1_1") (pintype "passive"))
      (node (ref "IC1") (pin "8") (pinfunction "PB7(XTAL2/TOSC2)_8") (pintype "bidirectional"))
      (node (ref "Q1") (pin "3") (pinfunction "3_3") (pintype "passive"))
    )
    (net (code "36") (name "unconnected-(IC1-ADC6-Pad19)") (class "Default")
      (node (ref "IC1") (pin "19") (pinfunction "ADC6_19") (pintype "bidirectional"))
    )
    (net (code "37") (name "unconnected-(IC1-ADC7-Pad22)") (class "Default")
      (node (ref "IC1") (pin "22") (pinfunction "ADC7_22") (pintype "bidirectional"))
    )
    (net (code "38") (name "unconnected-(IC1-AREF-Pad20)") (class "Default")
      (node (ref "IC1") (pin "20") (pinfunction "AREF_20") (pintype "passive"))
    )
    (net (code "39") (name "unconnected-(IC1-PB0(ICP)-Pad12)") (class "Default")
      (node (ref "IC1") (pin "12") (pinfunction "PB0(ICP)_12") (pintype "bidirectional"))
    )
    (net (code "40") (name "unconnected-(IC1-PC4(ADC4{slash}SDA)-Pad27)") (class "Default")
      (node (ref "IC1") (pin "27") (pinfunction "PC4(ADC4/SDA)_27") (pintype "bidirectional"))
    )
    (net (code "41") (name "unconnected-(IC1-PC5(ADC5{slash}SCL)-Pad28)") (class "Default")
      (node (ref "IC1") (pin "28") (pinfunction "PC5(ADC5/SCL)_28") (pintype "bidirectional"))
    )
    (net (code "42") (name "unconnected-(Q1-Pad2)") (class "Default")
      (node (ref "Q1") (pin "2") (pinfunction "2_2") (pintype "passive"))
    )
    (net (code "43") (name "unconnected-(Q1-Pad4)") (class "Default")
      (node (ref "Q1") (pin "4") (pinfunction "4_4") (pintype "passive"))
    )
  )
)
